# ACS770_breakout_v0_2.net
KiCad netlist of a schematic drawn in EAGLE
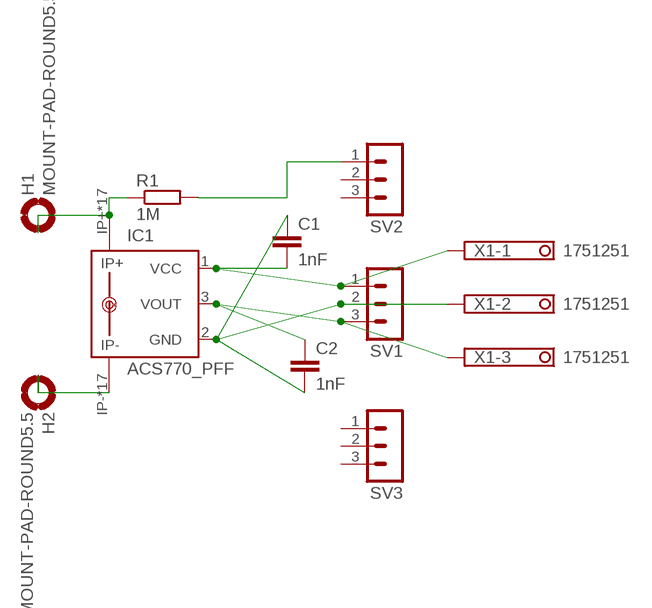
[diagram p0: schematic, sheet 1]

(export (version "E")
  (design (tool "Eeschema 10.0.6"))
  (components
    (comp (ref "C1")
      (value "1nF")
      (footprint "eagle-import:C025-025X050")
      (libsource (lib "eagle-import") (part "C-EU025-025X050"))
    )
    (comp (ref "C2")
      (value "1nF")
      (footprint "eagle-import:C025-025X050")
      (libsource (lib "eagle-import") (part "C-EU025-025X050"))
    )
    (comp (ref "H1")
      (value "MOUNT-PAD-ROUND5.5")
      (footprint "eagle-import:5,5-PAD")
      (libsource (lib "eagle-import") (part "MOUNT-PAD-ROUND5.5"))
    )
    (comp (ref "H2")
      (value "MOUNT-PAD-ROUND5.5")
      (footprint "eagle-import:5,5-PAD")
      (libsource (lib "eagle-import") (part "MOUNT-PAD-ROUND5.5"))
    )
    (comp (ref "IC1")
      (value "ACS770_PFF")
      (footprint "eagle-import:CB-PFF")
      (fields (field (name "MPN") "ACS758LCB-050B-PFF-T"))
      (libsource (lib "eagle-import") (part "ACS758LCB-050B-PFF-T"))
    )
    (comp (ref "R1")
      (value "1M")
      (footprint "eagle-import:0411_15")
      (libsource (lib "eagle-import") (part "R-EU_0411/15"))
    )
    (comp (ref "SV1")
      (value "MA03-1")
      (footprint "eagle-import:MA03-1")
      (libsource (lib "eagle-import") (part "MA03-1"))
    )
    (comp (ref "SV2")
      (value "MA03-1")
      (footprint "eagle-import:MA03-1")
      (libsource (lib "eagle-import") (part "MA03-1"))
    )
    (comp (ref "SV3")
      (value "MA03-1")
      (footprint "eagle-import:MA03-1")
      (libsource (lib "eagle-import") (part "MA03-1"))
    )
    (comp (ref "X1")
      (value "1751251")
      (footprint "eagle-import:1751251")
      (libsource (lib "eagle-import") (part "1751251"))
    )
  )
  (nets
    (net (code "1") (name "Net-(H1-MOUNT)") (class "Default")
      (node (ref "H1") (pin "B5,5") (pinfunction "MOUNT_B5,5") (pintype "passive"))
      (node (ref "IC1") (pin "IP+") (pinfunction "IP+_IP+") (pintype "passive"))
      (node (ref "IC1") (pin "IP+@10") (pinfunction "IP+_IP+@10") (pintype "passive"))
      (node (ref "IC1") (pin "IP+@11") (pinfunction "IP+_IP+@11") (pintype "passive"))
      (node (ref "IC1") (pin "IP+@12") (pinfunction "IP+_IP+@12") (pintype "passive"))
      (node (ref "IC1") (pin "IP+@13") (pinfunction "IP+_IP+@13") (pintype "passive"))
      (node (ref "IC1") (pin "IP+@14") (pinfunction "IP+_IP+@14") (pintype "passive"))
      (node (ref "IC1") (pin "IP+@15") (pinfunction "IP+_IP+@15") (pintype "passive"))
      (node (ref "IC1") (pin "IP+@16") (pinfunction "IP+_IP+@16") (pintype "passive"))
      (node (ref "IC1") (pin "IP+@17") (pinfunction "IP+_IP+@17") (pintype "passive"))
      (node (ref "IC1") (pin "IP+@2") (pinfunction "IP+_IP+@2") (pintype "passive"))
      (node (ref "IC1") (pin "IP+@3") (pinfunction "IP+_IP+@3") (pintype "passive"))
      (node (ref "IC1") (pin "IP+@4") (pinfunction "IP+_IP+@4") (pintype "passive"))
      (node (ref "IC1") (pin "IP+@5") (pinfunction "IP+_IP+@5") (pintype "passive"))
      (node (ref "IC1") (pin "IP+@6") (pinfunction "IP+_IP+@6") (pintype "passive"))
      (node (ref "IC1") (pin "IP+@7") (pinfunction "IP+_IP+@7") (pintype "passive"))
      (node (ref "IC1") (pin "IP+@8") (pinfunction "IP+_IP+@8") (pintype "passive"))
      (node (ref "IC1") (pin "IP+@9") (pinfunction "IP+_IP+@9") (pintype "passive"))
      (node (ref "R1") (pin "1") (pinfunction "1_1") (pintype "passive"))
    )
    (net (code "2") (name "Net-(H2-MOUNT)") (class "Default")
      (node (ref "H2") (pin "B5,5") (pinfunction "MOUNT_B5,5") (pintype "passive"))
      (node (ref "IC1") (pin "IP-") (pinfunction "IP-_IP-") (pintype "passive"))
      (node (ref "IC1") (pin "IP-@10") (pinfunction "IP-_IP-@10") (pintype "passive"))
      (node (ref "IC1") (pin "IP-@11") (pinfunction "IP-_IP-@11") (pintype "passive"))
      (node (ref "IC1") (pin "IP-@12") (pinfunction "IP-_IP-@12") (pintype "passive"))
      (node (ref "IC1") (pin "IP-@13") (pinfunction "IP-_IP-@13") (pintype "passive"))
      (node (ref "IC1") (pin "IP-@14") (pinfunction "IP-_IP-@14") (pintype "passive"))
      (node (ref "IC1") (pin "IP-@15") (pinfunction "IP-_IP-@15") (pintype "passive"))
      (node (ref "IC1") (pin "IP-@16") (pinfunction "IP-_IP-@16") (pintype "passive"))
      (node (ref "IC1") (pin "IP-@17") (pinfunction "IP-_IP-@17") (pintype "passive"))
      (node (ref "IC1") (pin "IP-@2") (pinfunction "IP-_IP-@2") (pintype "passive"))
      (node (ref "IC1") (pin "IP-@3") (pinfunction "IP-_IP-@3") (pintype "passive"))
      (node (ref "IC1") (pin "IP-@4") (pinfunction "IP-_IP-@4") (pintype "passive"))
      (node (ref "IC1") (pin "IP-@5") (pinfunction "IP-_IP-@5") (pintype "passive"))
      (node (ref "IC1") (pin "IP-@6") (pinfunction "IP-_IP-@6") (pintype "passive"))
      (node (ref "IC1") (pin "IP-@7") (pinfunction "IP-_IP-@7") (pintype "passive"))
      (node (ref "IC1") (pin "IP-@8") (pinfunction "IP-_IP-@8") (pintype "passive"))
      (node (ref "IC1") (pin "IP-@9") (pinfunction "IP-_IP-@9") (pintype "passive"))
    )
    (net (code "3") (name "Net-(IC1-GND)") (class "Default")
      (node (ref "C1") (pin "1") (pinfunction "1_1") (pintype "passive"))
      (node (ref "C2") (pin "2") (pinfunction "2_2") (pintype "passive"))
      (node (ref "IC1") (pin "2") (pinfunction "GND_2") (pintype "power_in"))
      (node (ref "SV1") (pin "2") (pinfunction "2_2") (pintype "passive"))
      (node (ref "X1") (pin "2") (pinfunction "K_2") (pintype "passive"))
    )
    (net (code "4") (name "Net-(IC1-VCC)") (class "Default")
      (node (ref "C1") (pin "2") (pinfunction "2_2") (pintype "passive"))
      (node (ref "IC1") (pin "1") (pinfunction "VCC_1") (pintype "power_in"))
      (node (ref "SV1") (pin "1") (pinfunction "1_1") (pintype "passive"))
      (node (ref "X1") (pin "1") (pinfunction "K_1") (pintype "passive"))
    )
    (net (code "5") (name "Net-(IC1-VOUT)") (class "Default")
      (node (ref "C2") (pin "1") (pinfunction "1_1") (pintype "passive"))
      (node (ref "IC1") (pin "3") (pinfunction "VOUT_3") (pintype "output"))
      (node (ref "SV1") (pin "3") (pinfunction "3_3") (pintype "passive"))
      (node (ref "X1") (pin "3") (pinfunction "K_3") (pintype "passive"))
    )
    (net (code "6") (name "Net-(R1-Pad2)") (class "Default")
      (node (ref "R1") (pin "2") (pinfunction "2_2") (pintype "passive"))
      (node (ref "SV2") (pin "1") (pinfunction "1_1") (pintype "passive"))
    )
    (net (code "7") (name "unconnected-(SV2-Pad2)") (class "Default")
      (node (ref "SV2") (pin "2") (pinfunction "2_2") (pintype "passive"))
    )
    (net (code "8") (name "unconnected-(SV2-Pad3)") (class "Default")
      (node (ref "SV2") (pin "3") (pinfunction "3_3") (pintype "passive"))
    )
    (net (code "9") (name "unconnected-(SV3-Pad1)") (class "Default")
      (node (ref "SV3") (pin "1") (pinfunction "1_1") (pintype "passive"))
    )
    (net (code "10") (name "unconnected-(SV3-Pad2)") (class "Default")
      (node (ref "SV3") (pin "2") (pinfunction "2_2") (pintype "passive"))
    )
    (net (code "11") (name "unconnected-(SV3-Pad3)") (class "Default")
      (node (ref "SV3") (pin "3") (pinfunction "3_3") (pintype "passive"))
    )
  )
)
